# Clock.net
KiCad netlist of a schematic drawn in Altium Designer
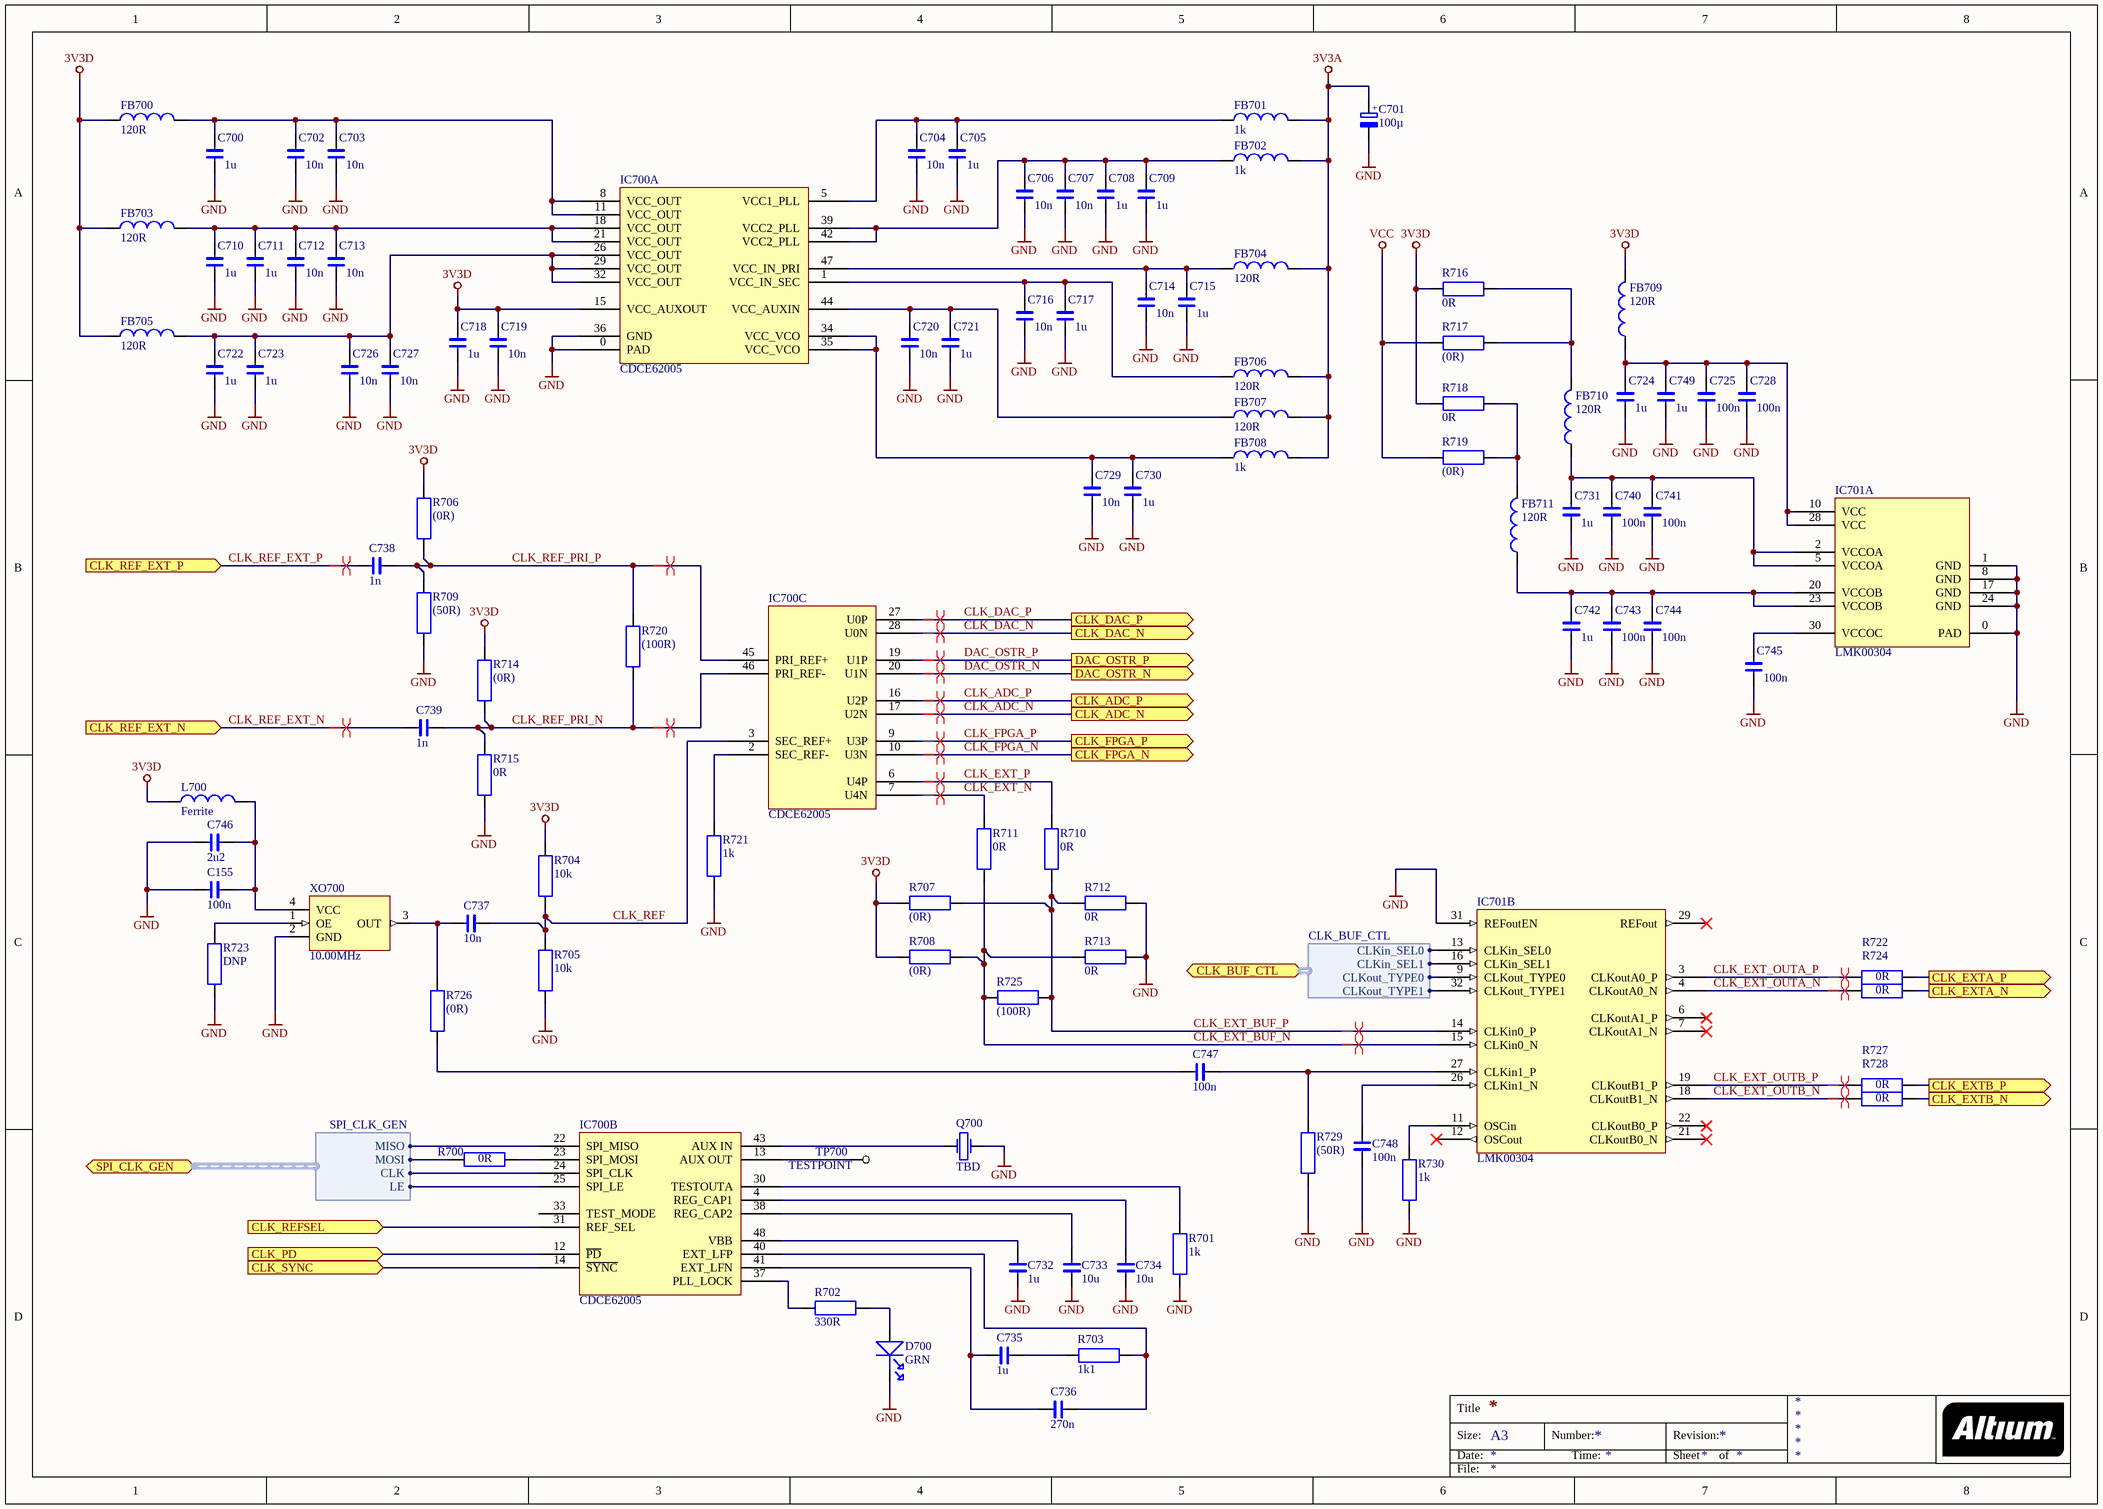
[diagram p0: Clock.SchDoc]

(export (version "E")
  (design (tool "Eeschema 10.0.6"))
  (components
    (comp (ref "C155")
      (value "100n")
      (footprint "0603 SMALL OUTLINE")
      (description "C")
      (libsource (lib "RCL") (part "C"))
    )
    (comp (ref "C700")
      (value "1u")
      (footprint "0603 SMALL OUTLINE")
      (description "C")
      (libsource (lib "RCL") (part "C"))
    )
    (comp (ref "C701")
      (value "100µ")
      (footprint "SMD_ELKO_6.3")
      (description "EEH-ZA1E101XP")
      (libsource (lib "RCL") (part "ELCO"))
    )
    (comp (ref "C702") (value "10n") (footprint "0402") (description "C") (libsource (lib "RCL") (part "C")))
    (comp (ref "C703") (value "10n") (footprint "0402") (description "C") (libsource (lib "RCL") (part "C")))
    (comp (ref "C704") (value "10n") (footprint "0402") (description "C") (libsource (lib "RCL") (part "C")))
    (comp (ref "C705")
      (value "1u")
      (footprint "0603 SMALL OUTLINE")
      (description "C")
      (libsource (lib "RCL") (part "C"))
    )
    (comp (ref "C706") (value "10n") (footprint "0402") (description "C") (libsource (lib "RCL") (part "C")))
    (comp (ref "C707") (value "10n") (footprint "0402") (description "C") (libsource (lib "RCL") (part "C")))
    (comp (ref "C708")
      (value "1u")
      (footprint "0603 SMALL OUTLINE")
      (description "C")
      (libsource (lib "RCL") (part "C"))
    )
    (comp (ref "C709")
      (value "1u")
      (footprint "0603 SMALL OUTLINE")
      (description "C")
      (libsource (lib "RCL") (part "C"))
    )
    (comp (ref "C710")
      (value "1u")
      (footprint "0603 SMALL OUTLINE")
      (description "C")
      (libsource (lib "RCL") (part "C"))
    )
    (comp (ref "C711")
      (value "1u")
      (footprint "0603 SMALL OUTLINE")
      (description "C")
      (libsource (lib "RCL") (part "C"))
    )
    (comp (ref "C712") (value "10n") (footprint "0402") (description "C") (libsource (lib "RCL") (part "C")))
    (comp (ref "C713") (value "10n") (footprint "0402") (description "C") (libsource (lib "RCL") (part "C")))
    (comp (ref "C714") (value "10n") (footprint "0402") (description "C") (libsource (lib "RCL") (part "C")))
    (comp (ref "C715")
      (value "1u")
      (footprint "0603 SMALL OUTLINE")
      (description "C")
      (libsource (lib "RCL") (part "C"))
    )
    (comp (ref "C716") (value "10n") (footprint "0402") (description "C") (libsource (lib "RCL") (part "C")))
    (comp (ref "C717")
      (value "1u")
      (footprint "0603 SMALL OUTLINE")
      (description "C")
      (libsource (lib "RCL") (part "C"))
    )
    (comp (ref "C718")
      (value "1u")
      (footprint "0603 SMALL OUTLINE")
      (description "C")
      (libsource (lib "RCL") (part "C"))
    )
    (comp (ref "C719") (value "10n") (footprint "0402") (description "C") (libsource (lib "RCL") (part "C")))
    (comp (ref "C720") (value "10n") (footprint "0402") (description "C") (libsource (lib "RCL") (part "C")))
    (comp (ref "C721")
      (value "1u")
      (footprint "0603 SMALL OUTLINE")
      (description "C")
      (libsource (lib "RCL") (part "C"))
    )
    (comp (ref "C722")
      (value "1u")
      (footprint "0603 SMALL OUTLINE")
      (description "C")
      (libsource (lib "RCL") (part "C"))
    )
    (comp (ref "C723")
      (value "1u")
      (footprint "0603 SMALL OUTLINE")
      (description "C")
      (libsource (lib "RCL") (part "C"))
    )
    (comp (ref "C724")
      (value "1u")
      (footprint "0603 SMALL OUTLINE")
      (description "C")
      (libsource (lib "RCL") (part "C"))
    )
    (comp (ref "C725") (value "100n") (footprint "0402") (description "C") (libsource (lib "RCL") (part "C")))
    (comp (ref "C726") (value "10n") (footprint "0402") (description "C") (libsource (lib "RCL") (part "C")))
    (comp (ref "C727") (value "10n") (footprint "0402") (description "C") (libsource (lib "RCL") (part "C")))
    (comp (ref "C728") (value "100n") (footprint "0402") (description "C") (libsource (lib "RCL") (part "C")))
    (comp (ref "C729") (value "10n") (footprint "0402") (description "C") (libsource (lib "RCL") (part "C")))
    (comp (ref "C730")
      (value "1u")
      (footprint "0603 SMALL OUTLINE")
      (description "C")
      (libsource (lib "RCL") (part "C"))
    )
    (comp (ref "C731")
      (value "1u")
      (footprint "0603 SMALL OUTLINE")
      (description "C")
      (libsource (lib "RCL") (part "C"))
    )
    (comp (ref "C732")
      (value "1u")
      (footprint "0603 SMALL OUTLINE")
      (description "C")
      (libsource (lib "RCL") (part "C"))
    )
    (comp (ref "C733")
      (value "10u")
      (footprint "0805 SMALL OUTLINE")
      (description "C")
      (libsource (lib "RCL") (part "C"))
    )
    (comp (ref "C734")
      (value "10u")
      (footprint "0805 SMALL OUTLINE")
      (description "C")
      (libsource (lib "RCL") (part "C"))
    )
    (comp (ref "C735")
      (value "1u")
      (footprint "0603 SMALL OUTLINE")
      (description "C")
      (libsource (lib "RCL") (part "C"))
    )
    (comp (ref "C736")
      (value "270n")
      (footprint "0603 SMALL OUTLINE")
      (description "C")
      (libsource (lib "RCL") (part "C"))
    )
    (comp (ref "C737")
      (value "10n")
      (footprint "0603 SMALL OUTLINE")
      (description "C")
      (libsource (lib "RCL") (part "C"))
    )
    (comp (ref "C738")
      (value "1n")
      (footprint "0603 SMALL OUTLINE")
      (description "C")
      (libsource (lib "RCL") (part "C"))
    )
    (comp (ref "C739")
      (value "1n")
      (footprint "0603 SMALL OUTLINE")
      (description "C")
      (libsource (lib "RCL") (part "C"))
    )
    (comp (ref "C740") (value "100n") (footprint "0402") (description "C") (libsource (lib "RCL") (part "C")))
    (comp (ref "C741") (value "100n") (footprint "0402") (description "C") (libsource (lib "RCL") (part "C")))
    (comp (ref "C742")
      (value "1u")
      (footprint "0603 SMALL OUTLINE")
      (description "C")
      (libsource (lib "RCL") (part "C"))
    )
    (comp (ref "C743") (value "100n") (footprint "0402") (description "C") (libsource (lib "RCL") (part "C")))
    (comp (ref "C744") (value "100n") (footprint "0402") (description "C") (libsource (lib "RCL") (part "C")))
    (comp (ref "C745") (value "100n") (footprint "0402") (description "C") (libsource (lib "RCL") (part "C")))
    (comp (ref "C746")
      (value "2u2")
      (footprint "0603 SMALL OUTLINE")
      (description "C")
      (libsource (lib "RCL") (part "C"))
    )
    (comp (ref "C747")
      (value "100n")
      (footprint "0603 SMALL OUTLINE")
      (description "C")
      (libsource (lib "RCL") (part "C"))
    )
    (comp (ref "C748") (value "100n") (footprint "0402") (description "C") (libsource (lib "RCL") (part "C")))
    (comp (ref "C749")
      (value "1u")
      (footprint "0603 SMALL OUTLINE")
      (description "C")
      (libsource (lib "RCL") (part "C"))
    )
    (comp (ref "D700")
      (value "GRN")
      (footprint "LED SMD 0603")
      (description "WURTH 150060VS75000")
      (libsource (lib "OPTO1") (part "LED SMD"))
    )
    (comp (ref "FB700")
      (value "120R")
      (footprint "0805 SMALL OUTLINE")
      (description "L")
      (libsource (lib "RCL") (part "L"))
    )
    (comp (ref "FB701")
      (value "1k")
      (footprint "0805 SMALL OUTLINE")
      (description "L")
      (libsource (lib "RCL") (part "L"))
    )
    (comp (ref "FB702")
      (value "1k")
      (footprint "0805 SMALL OUTLINE")
      (description "L")
      (libsource (lib "RCL") (part "L"))
    )
    (comp (ref "FB703")
      (value "120R")
      (footprint "0805 SMALL OUTLINE")
      (description "L")
      (libsource (lib "RCL") (part "L"))
    )
    (comp (ref "FB704")
      (value "120R")
      (footprint "0805 SMALL OUTLINE")
      (description "L")
      (libsource (lib "RCL") (part "L"))
    )
    (comp (ref "FB705")
      (value "120R")
      (footprint "0805 SMALL OUTLINE")
      (description "L")
      (libsource (lib "RCL") (part "L"))
    )
    (comp (ref "FB706")
      (value "120R")
      (footprint "0805 SMALL OUTLINE")
      (description "L")
      (libsource (lib "RCL") (part "L"))
    )
    (comp (ref "FB707")
      (value "120R")
      (footprint "0805 SMALL OUTLINE")
      (description "L")
      (libsource (lib "RCL") (part "L"))
    )
    (comp (ref "FB708")
      (value "1k")
      (footprint "0805 SMALL OUTLINE")
      (description "L")
      (libsource (lib "RCL") (part "L"))
    )
    (comp (ref "FB709")
      (value "120R")
      (footprint "0805 SMALL OUTLINE")
      (description "L")
      (libsource (lib "RCL") (part "L"))
    )
    (comp (ref "FB710")
      (value "120R")
      (footprint "0805 SMALL OUTLINE")
      (description "L")
      (libsource (lib "RCL") (part "L"))
    )
    (comp (ref "FB711")
      (value "120R")
      (footprint "0805 SMALL OUTLINE")
      (description "L")
      (libsource (lib "RCL") (part "L"))
    )
    (comp (ref "IC700")
      (value "CDCE62005")
      (footprint "48VQFN")
      (description "Five/Ten Output Clock Generator/Jitter Cleaner With Integrated Dual VCOs")
      (libsource (lib "Private") (part "CDCE62005"))
    )
    (comp (ref "IC701")
      (value "LMK00304")
      (footprint "WQFN32_LONG")
      (description "3-GHz 4-Output Differential Clock Buffer/Level Translator")
      (libsource (lib "Private") (part "LMK00304"))
    )
    (comp (ref "L700")
      (value "Ferrite")
      (footprint "0805")
      (description "L")
      (libsource (lib "RCL") (part "L"))
    )
    (comp (ref "Q700")
      (value "TBD")
      (footprint "XTAL_SMD_60_35")
      (description "XX MHz")
      (libsource (lib "RCL") (part "CRYSTAL"))
    )
    (comp (ref "R700")
      (value "0R")
      (footprint "0603 SMALL OUTLINE")
      (description "R")
      (libsource (lib "RCL") (part "R"))
    )
    (comp (ref "R701")
      (value "1k")
      (footprint "0603 SMALL OUTLINE")
      (description "R")
      (libsource (lib "RCL") (part "R"))
    )
    (comp (ref "R702")
      (value "330R")
      (footprint "0603 SMALL OUTLINE")
      (description "R")
      (libsource (lib "RCL") (part "R"))
    )
    (comp (ref "R703")
      (value "1k1")
      (footprint "0603 SMALL OUTLINE")
      (description "R")
      (libsource (lib "RCL") (part "R"))
    )
    (comp (ref "R704")
      (value "10k")
      (footprint "0603 SMALL OUTLINE")
      (description "R")
      (libsource (lib "RCL") (part "R"))
    )
    (comp (ref "R705")
      (value "10k")
      (footprint "0603 SMALL OUTLINE")
      (description "R")
      (libsource (lib "RCL") (part "R"))
    )
    (comp (ref "R706") (value "(0R)") (footprint "0402") (description "R") (libsource (lib "RCL") (part "R")))
    (comp (ref "R707") (value "(0R)") (footprint "0402") (description "R") (libsource (lib "RCL") (part "R")))
    (comp (ref "R708") (value "(0R)") (footprint "0402") (description "R") (libsource (lib "RCL") (part "R")))
    (comp (ref "R709")
      (value "(50R)")
      (footprint "0402")
      (description "R")
      (libsource (lib "RCL") (part "R"))
    )
    (comp (ref "R710") (value "0R") (footprint "0402") (description "R") (libsource (lib "RCL") (part "R")))
    (comp (ref "R711") (value "0R") (footprint "0402") (description "R") (libsource (lib "RCL") (part "R")))
    (comp (ref "R712") (value "0R") (footprint "0402") (description "R") (libsource (lib "RCL") (part "R")))
    (comp (ref "R713") (value "0R") (footprint "0402") (description "R") (libsource (lib "RCL") (part "R")))
    (comp (ref "R714") (value "(0R)") (footprint "0402") (description "R") (libsource (lib "RCL") (part "R")))
    (comp (ref "R715") (value "0R") (footprint "0402") (description "R") (libsource (lib "RCL") (part "R")))
    (comp (ref "R716")
      (value "0R")
      (footprint "0603 SMALL OUTLINE")
      (description "R")
      (libsource (lib "RCL") (part "R"))
    )
    (comp (ref "R717")
      (value "(0R)")
      (footprint "0603 SMALL OUTLINE")
      (description "R")
      (libsource (lib "RCL") (part "R"))
    )
    (comp (ref "R718")
      (value "0R")
      (footprint "0603 SMALL OUTLINE")
      (description "R")
      (libsource (lib "RCL") (part "R"))
    )
    (comp (ref "R719")
      (value "(0R)")
      (footprint "0603 SMALL OUTLINE")
      (description "R")
      (libsource (lib "RCL") (part "R"))
    )
    (comp (ref "R720")
      (value "(100R)")
      (footprint "0402")
      (description "R")
      (libsource (lib "RCL") (part "R"))
    )
    (comp (ref "R721")
      (value "1k")
      (footprint "0603 SMALL OUTLINE")
      (description "R")
      (libsource (lib "RCL") (part "R"))
    )
    (comp (ref "R722") (value "0R") (footprint "0402") (description "R") (libsource (lib "RCL") (part "R")))
    (comp (ref "R723")
      (value "DNP")
      (footprint "0603 SMALL OUTLINE")
      (description "R")
      (libsource (lib "RCL") (part "R"))
    )
    (comp (ref "R724") (value "0R") (footprint "0402") (description "R") (libsource (lib "RCL") (part "R")))
    (comp (ref "R725")
      (value "(100R)")
      (footprint "0402")
      (description "R")
      (libsource (lib "RCL") (part "R"))
    )
    (comp (ref "R726")
      (value "(0R)")
      (footprint "0603 SMALL OUTLINE")
      (description "R")
      (libsource (lib "RCL") (part "R"))
    )
    (comp (ref "R727") (value "0R") (footprint "0402") (description "R") (libsource (lib "RCL") (part "R")))
    (comp (ref "R728") (value "0R") (footprint "0402") (description "R") (libsource (lib "RCL") (part "R")))
    (comp (ref "R729")
      (value "(50R)")
      (footprint "0402")
      (description "R")
      (libsource (lib "RCL") (part "R"))
    )
    (comp (ref "R730")
      (value "1k")
      (footprint "0603 SMALL OUTLINE")
      (description "R")
      (libsource (lib "RCL") (part "R"))
    )
    (comp (ref "TP700")
      (value "TESTPOINT")
      (footprint "TEST_PAD_50")
      (libsource (lib "CONNECT1") (part "TESTPOINT"))
    )
    (comp (ref "XO700")
      (value "10.00MHz")
      (footprint "AST3TQ")
      (description "AST3TQ-10.00MHz-1")
      (libsource (lib "SPECIAL1") (part "OSZILLATOR_4P SMD"))
    )
  )
  (nets
    (net (code "3") (name "/CLK") (class "Default")
      (node (ref "IC700") (pin "24") (pinfunction "SPI_CLK_24") (pintype "passive"))
    )
    (net (code "4") (name "/CLK_ADC_N") (class "Default")
      (node (ref "IC700") (pin "17") (pinfunction "U2N_17") (pintype "passive"))
    )
    (net (code "5") (name "/CLK_ADC_P") (class "Default")
      (node (ref "IC700") (pin "16") (pinfunction "U2P_16") (pintype "passive"))
    )
    (net (code "6") (name "/CLK_DAC_N") (class "Default")
      (node (ref "IC700") (pin "28") (pinfunction "U0N_28") (pintype "passive"))
    )
    (net (code "7") (name "/CLK_DAC_P") (class "Default")
      (node (ref "IC700") (pin "27") (pinfunction "U0P_27") (pintype "passive"))
    )
    (net (code "8") (name "/CLK_EXTA_N") (class "Default")
      (node (ref "R724") (pin "2") (pinfunction "2_2") (pintype "passive"))
    )
    (net (code "9") (name "/CLK_EXTA_P") (class "Default")
      (node (ref "R722") (pin "2") (pinfunction "2_2") (pintype "passive"))
    )
    (net (code "10") (name "/CLK_EXTB_N") (class "Default")
      (node (ref "R728") (pin "2") (pinfunction "2_2") (pintype "passive"))
    )
    (net (code "11") (name "/CLK_EXTB_P") (class "Default")
      (node (ref "R727") (pin "2") (pinfunction "2_2") (pintype "passive"))
    )
    (net (code "12") (name "/CLK_EXT_BUF_N") (class "Default")
      (node (ref "IC701") (pin "15") (pinfunction "CLKin0_N_15") (pintype "input"))
      (node (ref "R708") (pin "1") (pinfunction "1_1") (pintype "passive"))
      (node (ref "R711") (pin "1") (pinfunction "1_1") (pintype "passive"))
      (node (ref "R713") (pin "2") (pinfunction "2_2") (pintype "passive"))
      (node (ref "R725") (pin "1") (pinfunction "1_1") (pintype "passive"))
    )
    (net (code "13") (name "/CLK_EXT_BUF_P") (class "Default")
      (node (ref "IC701") (pin "14") (pinfunction "CLKin0_P_14") (pintype "input"))
      (node (ref "R707") (pin "1") (pinfunction "1_1") (pintype "passive"))
      (node (ref "R710") (pin "1") (pinfunction "1_1") (pintype "passive"))
      (node (ref "R712") (pin "2") (pinfunction "2_2") (pintype "passive"))
      (node (ref "R725") (pin "2") (pinfunction "2_2") (pintype "passive"))
    )
    (net (code "14") (name "/CLK_EXT_N") (class "Default")
      (node (ref "IC700") (pin "7") (pinfunction "U4N_7") (pintype "passive"))
      (node (ref "R711") (pin "2") (pinfunction "2_2") (pintype "passive"))
    )
    (net (code "15") (name "/CLK_EXT_OUTA_N") (class "Default")
      (node (ref "IC701") (pin "4") (pinfunction "CLKoutA0_N_4") (pintype "output"))
      (node (ref "R724") (pin "1") (pinfunction "1_1") (pintype "passive"))
    )
    (net (code "16") (name "/CLK_EXT_OUTA_P") (class "Default")
      (node (ref "IC701") (pin "3") (pinfunction "CLKoutA0_P_3") (pintype "output"))
      (node (ref "R722") (pin "1") (pinfunction "1_1") (pintype "passive"))
    )
    (net (code "17") (name "/CLK_EXT_OUTB_N") (class "Default")
      (node (ref "IC701") (pin "18") (pinfunction "CLKoutB1_N_18") (pintype "output"))
      (node (ref "R728") (pin "1") (pinfunction "1_1") (pintype "passive"))
    )
    (net (code "18") (name "/CLK_EXT_OUTB_P") (class "Default")
      (node (ref "IC701") (pin "19") (pinfunction "CLKoutB1_P_19") (pintype "output"))
      (node (ref "R727") (pin "1") (pinfunction "1_1") (pintype "passive"))
    )
    (net (code "19") (name "/CLK_EXT_P") (class "Default")
      (node (ref "IC700") (pin "6") (pinfunction "U4P_6") (pintype "passive"))
      (node (ref "R710") (pin "2") (pinfunction "2_2") (pintype "passive"))
    )
    (net (code "20") (name "/CLK_FPGA_N") (class "Default")
      (node (ref "IC700") (pin "10") (pinfunction "U3N_10") (pintype "passive"))
    )
    (net (code "21") (name "/CLK_FPGA_P") (class "Default")
      (node (ref "IC700") (pin "9") (pinfunction "U3P_9") (pintype "passive"))
    )
    (net (code "22") (name "/CLK_PD") (class "Default")
      (node (ref "IC700") (pin "12") (pinfunction "~{PD}_12") (pintype "passive"))
    )
    (net (code "23") (name "/CLK_REF") (class "Default")
      (node (ref "C737") (pin "2") (pinfunction "2_2") (pintype "passive"))
      (node (ref "IC700") (pin "3") (pinfunction "SEC_REF+_3") (pintype "passive"))
      (node (ref "R704") (pin "1") (pinfunction "1_1") (pintype "passive"))
      (node (ref "R705") (pin "2") (pinfunction "2_2") (pintype "passive"))
    )
    (net (code "24") (name "/CLK_REFSEL") (class "Default")
      (node (ref "IC700") (pin "31") (pinfunction "REF_SEL_31") (pintype "passive"))
    )
    (net (code "25") (name "/CLK_REF_EXT_N") (class "Default")
      (node (ref "C739") (pin "1") (pinfunction "1_1") (pintype "passive"))
    )
    (net (code "26") (name "/CLK_REF_EXT_P") (class "Default")
      (node (ref "C738") (pin "1") (pinfunction "1_1") (pintype "passive"))
    )
    (net (code "27") (name "/CLK_REF_PRI_N") (class "Default")
      (node (ref "C739") (pin "2") (pinfunction "2_2") (pintype "passive"))
      (node (ref "IC700") (pin "46") (pinfunction "PRI_REF-_46") (pintype "passive"))
      (node (ref "R714") (pin "1") (pinfunction "1_1") (pintype "passive"))
      (node (ref "R715") (pin "2") (pinfunction "2_2") (pintype "passive"))
      (node (ref "R720") (pin "1") (pinfunction "1_1") (pintype "passive"))
    )
    (net (code "28") (name "/CLK_REF_PRI_P") (class "Default")
      (node (ref "C738") (pin "2") (pinfunction "2_2") (pintype "passive"))
      (node (ref "IC700") (pin "45") (pinfunction "PRI_REF+_45") (pintype "passive"))
      (node (ref "R706") (pin "1") (pinfunction "1_1") (pintype "passive"))
      (node (ref "R709") (pin "2") (pinfunction "2_2") (pintype "passive"))
      (node (ref "R720") (pin "2") (pinfunction "2_2") (pintype "passive"))
    )
    (net (code "29") (name "/CLK_SYNC") (class "Default")
      (node (ref "IC700") (pin "14") (pinfunction "~{SYNC}_14") (pintype "passive"))
    )
    (net (code "30") (name "/CLKin_SEL0") (class "Default")
      (node (ref "IC701") (pin "13") (pinfunction "CLKin_SEL0_13") (pintype "input"))
    )
    (net (code "31") (name "/CLKin_SEL1") (class "Default")
      (node (ref "IC701") (pin "16") (pinfunction "CLKin_SEL1_16") (pintype "input"))
    )
    (net (code "32") (name "/CLKout_TYPE0") (class "Default")
      (node (ref "IC701") (pin "9") (pinfunction "CLKout_TYPE0_9") (pintype "input"))
    )
    (net (code "33") (name "/CLKout_TYPE1") (class "Default")
      (node (ref "IC701") (pin "32") (pinfunction "CLKout_TYPE1_32") (pintype "input"))
    )
    (net (code "34") (name "/DAC_OSTR_N") (class "Default")
      (node (ref "IC700") (pin "20") (pinfunction "U1N_20") (pintype "passive"))
    )
    (net (code "35") (name "/DAC_OSTR_P") (class "Default")
      (node (ref "IC700") (pin "19") (pinfunction "U1P_19") (pintype "passive"))
    )
    (net (code "36") (name "/LE") (class "Default")
      (node (ref "IC700") (pin "25") (pinfunction "SPI_LE_25") (pintype "passive"))
    )
    (net (code "37") (name "/MISO") (class "Default")
      (node (ref "IC700") (pin "22") (pinfunction "SPI_MISO_22") (pintype "passive"))
    )
    (net (code "38") (name "/MOSI") (class "Default")
      (node (ref "R700") (pin "1") (pinfunction "1_1") (pintype "passive"))
    )
    (net (code "41") (name "3V3A") (class "Default")
      (node (ref "C701") (pin "1") (pinfunction "+_1") (pintype "passive"))
      (node (ref "FB701") (pin "2") (pinfunction "2_2") (pintype "passive"))
      (node (ref "FB702") (pin "2") (pinfunction "2_2") (pintype "passive"))
      (node (ref "FB704") (pin "2") (pinfunction "2_2") (pintype "passive"))
      (node (ref "FB706") (pin "2") (pinfunction "2_2") (pintype "passive"))
      (node (ref "FB707") (pin "2") (pinfunction "2_2") (pintype "passive"))
      (node (ref "FB708") (pin "2") (pinfunction "2_2") (pintype "passive"))
    )
    (net (code "42") (name "3V3D") (class "Default")
      (node (ref "C718") (pin "1") (pinfunction "1_1") (pintype "passive"))
      (node (ref "C719") (pin "1") (pinfunction "1_1") (pintype "passive"))
      (node (ref "FB700") (pin "1") (pinfunction "1_1") (pintype "passive"))
      (node (ref "FB703") (pin "1") (pinfunction "1_1") (pintype "passive"))
      (node (ref "FB705") (pin "1") (pinfunction "1_1") (pintype "passive"))
      (node (ref "FB709") (pin "2") (pinfunction "2_2") (pintype "passive"))
      (node (ref "IC700") (pin "15") (pinfunction "VCC_AUXOUT_15") (pintype "passive"))
      (node (ref "L700") (pin "1") (pinfunction "1_1") (pintype "passive"))
      (node (ref "R704") (pin "2") (pinfunction "2_2") (pintype "passive"))
      (node (ref "R706") (pin "2") (pinfunction "2_2") (pintype "passive"))
      (node (ref "R707") (pin "2") (pinfunction "2_2") (pintype "passive"))
      (node (ref "R708") (pin "2") (pinfunction "2_2") (pintype "passive"))
      (node (ref "R714") (pin "2") (pinfunction "2_2") (pintype "passive"))
      (node (ref "R716") (pin "2") (pinfunction "2_2") (pintype "passive"))
      (node (ref "R718") (pin "2") (pinfunction "2_2") (pintype "passive"))
    )
    (net (code "43") (name "GND") (class "Default")
      (node (ref "C155") (pin "2") (pinfunction "2_2") (pintype "passive"))
      (node (ref "C700") (pin "2") (pinfunction "2_2") (pintype "passive"))
      (node (ref "C701") (pin "2") (pinfunction "-_2") (pintype "passive"))
      (node (ref "C702") (pin "2") (pinfunction "2_2") (pintype "passive"))
      (node (ref "C703") (pin "2") (pinfunction "2_2") (pintype "passive"))
      (node (ref "C704") (pin "2") (pinfunction "2_2") (pintype "passive"))
      (node (ref "C705") (pin "2") (pinfunction "2_2") (pintype "passive"))
      (node (ref "C706") (pin "2") (pinfunction "2_2") (pintype "passive"))
      (node (ref "C707") (pin "2") (pinfunction "2_2") (pintype "passive"))
      (node (ref "C708") (pin "2") (pinfunction "2_2") (pintype "passive"))
      (node (ref "C709") (pin "2") (pinfunction "2_2") (pintype "passive"))
      (node (ref "C710") (pin "2") (pinfunction "2_2") (pintype "passive"))
      (node (ref "C711") (pin "2") (pinfunction "2_2") (pintype "passive"))
      (node (ref "C712") (pin "2") (pinfunction "2_2") (pintype "passive"))
      (node (ref "C713") (pin "2") (pinfunction "2_2") (pintype "passive"))
      (node (ref "C714") (pin "2") (pinfunction "2_2") (pintype "passive"))
      (node (ref "C715") (pin "2") (pinfunction "2_2") (pintype "passive"))
      (node (ref "C716") (pin "2") (pinfunction "2_2") (pintype "passive"))
      (node (ref "C717") (pin "2") (pinfunction "2_2") (pintype "passive"))
      (node (ref "C718") (pin "2") (pinfunction "2_2") (pintype "passive"))
      (node (ref "C719") (pin "2") (pinfunction "2_2") (pintype "passive"))
      (node (ref "C720") (pin "2") (pinfunction "2_2") (pintype "passive"))
      (node (ref "C721") (pin "2") (pinfunction "2_2") (pintype "passive"))
      (node (ref "C722") (pin "2") (pinfunction "2_2") (pintype "passive"))
      (node (ref "C723") (pin "2") (pinfunction "2_2") (pintype "passive"))
      (node (ref "C724") (pin "2") (pinfunction "2_2") (pintype "passive"))
      (node (ref "C725") (pin "2") (pinfunction "2_2") (pintype "passive"))
      (node (ref "C726") (pin "2") (pinfunction "2_2") (pintype "passive"))
      (node (ref "C727") (pin "2") (pinfunction "2_2") (pintype "passive"))
      (node (ref "C728") (pin "2") (pinfunction "2_2") (pintype "passive"))
      (node (ref "C729") (pin "2") (pinfunction "2_2") (pintype "passive"))
      (node (ref "C730") (pin "2") (pinfunction "2_2") (pintype "passive"))
      (node (ref "C731") (pin "2") (pinfunction "2_2") (pintype "passive"))
      (node (ref "C732") (pin "2") (pinfunction "2_2") (pintype "passive"))
      (node (ref "C733") (pin "2") (pinfunction "2_2") (pintype "passive"))
      (node (ref "C734") (pin "2") (pinfunction "2_2") (pintype "passive"))
      (node (ref "C740") (pin "2") (pinfunction "2_2") (pintype "passive"))
      (node (ref "C741") (pin "2") (pinfunction "2_2") (pintype "passive"))
      (node (ref "C742") (pin "2") (pinfunction "2_2") (pintype "passive"))
      (node (ref "C743") (pin "2") (pinfunction "2_2") (pintype "passive"))
      (node (ref "C744") (pin "2") (pinfunction "2_2") (pintype "passive"))
      (node (ref "C745") (pin "2") (pinfunction "2_2") (pintype "passive"))
      (node (ref "C746") (pin "2") (pinfunction "2_2") (pintype "passive"))
      (node (ref "C748") (pin "2") (pinfunction "2_2") (pintype "passive"))
      (node (ref "C749") (pin "2") (pinfunction "2_2") (pintype "passive"))
      (node (ref "D700") (pin "K") (pinfunction "K_K") (pintype "passive"))
      (node (ref "IC700") (pin "0") (pinfunction "PAD_0") (pintype "passive"))
      (node (ref "IC700") (pin "36") (pinfunction "GND_36") (pintype "passive"))
      (node (ref "IC701") (pin "0") (pinfunction "PAD_0") (pintype "power_in"))
      (node (ref "IC701") (pin "1") (pinfunction "GND_1") (pintype "power_in"))
      (node (ref "IC701") (pin "17") (pinfunction "GND_17") (pintype "power_in"))
      (node (ref "IC701") (pin "24") (pinfunction "GND_24") (pintype "power_in"))
      (node (ref "IC701") (pin "31") (pinfunction "REFoutEN_31") (pintype "input"))
      (node (ref "IC701") (pin "8") (pinfunction "GND_8") (pintype "power_in"))
      (node (ref "Q700") (pin "2") (pinfunction "2_2") (pintype "passive"))
      (node (ref "R701") (pin "2") (pinfunction "2_2") (pintype "passive"))
      (node (ref "R705") (pin "1") (pinfunction "1_1") (pintype "passive"))
      (node (ref "R709") (pin "1") (pinfunction "1_1") (pintype "passive"))
      (node (ref "R712") (pin "1") (pinfunction "1_1") (pintype "passive"))
      (node (ref "R713") (pin "1") (pinfunction "1_1") (pintype "passive"))
      (node (ref "R715") (pin "1") (pinfunction "1_1") (pintype "passive"))
      (node (ref "R721") (pin "1") (pinfunction "1_1") (pintype "passive"))
      (node (ref "R723") (pin "1") (pinfunction "1_1") (pintype "passive"))
      (node (ref "R729") (pin "1") (pinfunction "1_1") (pintype "passive"))
      (node (ref "R730") (pin "1") (pinfunction "1_1") (pintype "passive"))
      (node (ref "XO700") (pin "2") (pinfunction "GND_2") (pintype "power_in"))
    )
    (net (code "44") (name "Net-(C700-Pad1)") (class "Default")
      (node (ref "C700") (pin "1") (pinfunction "1_1") (pintype "passive"))
      (node (ref "C702") (pin "1") (pinfunction "1_1") (pintype "passive"))
      (node (ref "C703") (pin "1") (pinfunction "1_1") (pintype "passive"))
      (node (ref "FB700") (pin "2") (pinfunction "2_2") (pintype "passive"))
      (node (ref "IC700") (pin "11") (pinfunction "VCC_OUT_11") (pintype "passive"))
      (node (ref "IC700") (pin "8") (pinfunction "VCC_OUT_8") (pintype "passive"))
    )
    (net (code "45") (name "Net-(C706-Pad1)") (class "Default")
      (node (ref "C706") (pin "1") (pinfunction "1_1") (pintype "passive"))
      (node (ref "C707") (pin "1") (pinfunction "1_1") (pintype "passive"))
      (node (ref "C708") (pin "1") (pinfunction "1_1") (pintype "passive"))
      (node (ref "C709") (pin "1") (pinfunction "1_1") (pintype "passive"))
      (node (ref "FB702") (pin "1") (pinfunction "1_1") (pintype "passive"))
      (node (ref "IC700") (pin "39") (pinfunction "VCC2_PLL_39") (pintype "passive"))
      (node (ref "IC700") (pin "42") (pinfunction "VCC2_PLL_42") (pintype "passive"))
    )
    (net (code "46") (name "Net-(C710-Pad1)") (class "Default")
      (node (ref "C710") (pin "1") (pinfunction "1_1") (pintype "passive"))
      (node (ref "C711") (pin "1") (pinfunction "1_1") (pintype "passive"))
      (node (ref "C712") (pin "1") (pinfunction "1_1") (pintype "passive"))
      (node (ref "C713") (pin "1") (pinfunction "1_1") (pintype "passive"))
      (node (ref "FB703") (pin "2") (pinfunction "2_2") (pintype "passive"))
      (node (ref "IC700") (pin "18") (pinfunction "VCC_OUT_18") (pintype "passive"))
      (node (ref "IC700") (pin "21") (pinfunction "VCC_OUT_21") (pintype "passive"))
    )
    (net (code "47") (name "Net-(C722-Pad1)") (class "Default")
      (node (ref "C722") (pin "1") (pinfunction "1_1") (pintype "passive"))
      (node (ref "C723") (pin "1") (pinfunction "1_1") (pintype "passive"))
      (node (ref "C726") (pin "1") (pinfunction "1_1") (pintype "passive"))
      (node (ref "C727") (pin "1") (pinfunction "1_1") (pintype "passive"))
      (node (ref "FB705") (pin "2") (pinfunction "2_2") (pintype "passive"))
      (node (ref "IC700") (pin "26") (pinfunction "VCC_OUT_26") (pintype "passive"))
      (node (ref "IC700") (pin "29") (pinfunction "VCC_OUT_29") (pintype "passive"))
      (node (ref "IC700") (pin "32") (pinfunction "VCC_OUT_32") (pintype "passive"))
    )
    (net (code "48") (name "Net-(C724-Pad1)") (class "Default")
      (node (ref "C724") (pin "1") (pinfunction "1_1") (pintype "passive"))
      (node (ref "C725") (pin "1") (pinfunction "1_1") (pintype "passive"))
      (node (ref "C728") (pin "1") (pinfunction "1_1") (pintype "passive"))
      (node (ref "C749") (pin "1") (pinfunction "1_1") (pintype "passive"))
      (node (ref "FB709") (pin "1") (pinfunction "1_1") (pintype "passive"))
      (node (ref "IC701") (pin "10") (pinfunction "VCC_10") (pintype "power_in"))
      (node (ref "IC701") (pin "28") (pinfunction "VCC_28") (pintype "power_in"))
    )
    (net (code "49") (name "Net-(C729-Pad1)") (class "Default")
      (node (ref "C729") (pin "1") (pinfunction "1_1") (pintype "passive"))
      (node (ref "C730") (pin "1") (pinfunction "1_1") (pintype "passive"))
      (node (ref "FB708") (pin "1") (pinfunction "1_1") (pintype "passive"))
      (node (ref "IC700") (pin "34") (pinfunction "VCC_VCO_34") (pintype "passive"))
      (node (ref "IC700") (pin "35") (pinfunction "VCC_VCO_35") (pintype "passive"))
    )
    (net (code "50") (name "Net-(C731-Pad1)") (class "Default")
      (node (ref "C731") (pin "1") (pinfunction "1_1") (pintype "passive"))
      (node (ref "C740") (pin "1") (pinfunction "1_1") (pintype "passive"))
      (node (ref "C741") (pin "1") (pinfunction "1_1") (pintype "passive"))
      (node (ref "FB710") (pin "1") (pinfunction "1_1") (pintype "passive"))
      (node (ref "IC701") (pin "2") (pinfunction "VCCOA_2") (pintype "power_in"))
      (node (ref "IC701") (pin "5") (pinfunction "VCCOA_5") (pintype "power_in"))
    )
    (net (code "51") (name "Net-(C735-Pad2)") (class "Default")
      (node (ref "C735") (pin "2") (pinfunction "2_2") (pintype "passive"))
      (node (ref "R703") (pin "2") (pinfunction "2_2") (pintype "passive"))
    )
    (net (code "52") (name "Net-(C742-Pad1)") (class "Default")
      (node (ref "C742") (pin "1") (pinfunction "1_1") (pintype "passive"))
      (node (ref "C743") (pin "1") (pinfunction "1_1") (pintype "passive"))
      (node (ref "C744") (pin "1") (pinfunction "1_1") (pintype "passive"))
      (node (ref "FB711") (pin "1") (pinfunction "1_1") (pintype "passive"))
      (node (ref "IC701") (pin "20") (pinfunction "VCCOB_20") (pintype "power_in"))
      (node (ref "IC701") (pin "23") (pinfunction "VCCOB_23") (pintype "power_in"))
    )
    (net (code "53") (name "Net-(C747-Pad1)") (class "Default")
      (node (ref "C747") (pin "1") (pinfunction "1_1") (pintype "passive"))
      (node (ref "R726") (pin "2") (pinfunction "2_2") (pintype "passive"))
    )
    (net (code "54") (name "Net-(D700-PadA)") (class "Default")
      (node (ref "D700") (pin "A") (pinfunction "A_A") (pintype "passive"))
      (node (ref "R702") (pin "1") (pinfunction "1_1") (pintype "passive"))
    )
    (net (code "55") (name "Net-(FB710-Pad2)") (class "Default")
      (node (ref "FB710") (pin "2") (pinfunction "2_2") (pintype "passive"))
      (node (ref "R716") (pin "1") (pinfunction "1_1") (pintype "passive"))
      (node (ref "R717") (pin "1") (pinfunction "1_1") (pintype "passive"))
    )
    (net (code "56") (name "Net-(FB711-Pad2)") (class "Default")
      (node (ref "FB711") (pin "2") (pinfunction "2_2") (pintype "passive"))
      (node (ref "R718") (pin "1") (pinfunction "1_1") (pintype "passive"))
      (node (ref "R719") (pin "1") (pinfunction "1_1") (pintype "passive"))
    )
    (net (code "57") (name "Net-(IC700A-VCC1_PLL)") (class "Default")
      (node (ref "C704") (pin "1") (pinfunction "1_1") (pintype "passive"))
      (node (ref "C705") (pin "1") (pinfunction "1_1") (pintype "passive"))
      (node (ref "FB701") (pin "1") (pinfunction "1_1") (pintype "passive"))
      (node (ref "IC700") (pin "5") (pinfunction "VCC1_PLL_5") (pintype "passive"))
    )
    (net (code "58") (name "Net-(IC700A-VCC_AUXIN)") (class "Default")
      (node (ref "C720") (pin "1") (pinfunction "1_1") (pintype "passive"))
      (node (ref "C721") (pin "1") (pinfunction "1_1") (pintype "passive"))
      (node (ref "FB707") (pin "1") (pinfunction "1_1") (pintype "passive"))
      (node (ref "IC700") (pin "44") (pinfunction "VCC_AUXIN_44") (pintype "passive"))
    )
    (net (code "59") (name "Net-(IC700A-VCC_IN_PRI)") (class "Default")
      (node (ref "C714") (pin "1") (pinfunction "1_1") (pintype "passive"))
      (node (ref "C715") (pin "1") (pinfunction "1_1") (pintype "passive"))
      (node (ref "FB704") (pin "1") (pinfunction "1_1") (pintype "passive"))
      (node (ref "IC700") (pin "47") (pinfunction "VCC_IN_PRI_47") (pintype "passive"))
    )
    (net (code "60") (name "Net-(IC700A-VCC_IN_SEC)") (class "Default")
      (node (ref "C716") (pin "1") (pinfunction "1_1") (pintype "passive"))
      (node (ref "C717") (pin "1") (pinfunction "1_1") (pintype "passive"))
      (node (ref "FB706") (pin "1") (pinfunction "1_1") (pintype "passive"))
      (node (ref "IC700") (pin "1") (pinfunction "VCC_IN_SEC_1") (pintype "passive"))
    )
    (net (code "61") (name "Net-(IC700B-AUX_IN)") (class "Default")
      (node (ref "IC700") (pin "43") (pinfunction "AUX_IN_43") (pintype "passive"))
      (node (ref "Q700") (pin "1") (pinfunction "1_1") (pintype "passive"))
    )
    (net (code "62") (name "Net-(IC700B-AUX_OUT)") (class "Default")
      (node (ref "IC700") (pin "13") (pinfunction "AUX_OUT_13") (pintype "passive"))
      (node (ref "TP700") (pin "1") (pintype "passive"))
    )
    (net (code "63") (name "Net-(IC700B-EXT_LFN)") (class "Default")
      (node (ref "C735") (pin "1") (pinfunction "1_1") (pintype "passive"))
      (node (ref "C736") (pin "2") (pinfunction "2_2") (pintype "passive"))
      (node (ref "IC700") (pin "41") (pinfunction "EXT_LFN_41") (pintype "passive"))
    )
    (net (code "64") (name "Net-(IC700B-EXT_LFP)") (class "Default")
      (node (ref "C736") (pin "1") (pinfunction "1_1") (pintype "passive"))
      (node (ref "IC700") (pin "40") (pinfunction "EXT_LFP_40") (pintype "passive"))
      (node (ref "R703") (pin "1") (pinfunction "1_1") (pintype "passive"))
    )
    (net (code "65") (name "Net-(IC700B-PLL_LOCK)") (class "Default")
      (node (ref "IC700") (pin "37") (pinfunction "PLL_LOCK_37") (pintype "passive"))
      (node (ref "R702") (pin "2") (pinfunction "2_2") (pintype "passive"))
    )
    (net (code "66") (name "Net-(IC700B-REG_CAP1)") (class "Default")
      (node (ref "C734") (pin "1") (pinfunction "1_1") (pintype "passive"))
      (node (ref "IC700") (pin "4") (pinfunction "REG_CAP1_4") (pintype "passive"))
    )
    (net (code "67") (name "Net-(IC700B-REG_CAP2)") (class "Default")
      (node (ref "C733") (pin "1") (pinfunction "1_1") (pintype "passive"))
      (node (ref "IC700") (pin "38") (pinfunction "REG_CAP2_38") (pintype "passive"))
    )
    (net (code "68") (name "Net-(IC700B-SPI_MOSI)") (class "Default")
      (node (ref "IC700") (pin "23") (pinfunction "SPI_MOSI_23") (pintype "passive"))
      (node (ref "R700") (pin "2") (pinfunction "2_2") (pintype "passive"))
    )
    (net (code "69") (name "Net-(IC700B-TESTOUTA)") (class "Default")
      (node (ref "IC700") (pin "30") (pinfunction "TESTOUTA_30") (pintype "passive"))
      (node (ref "R701") (pin "1") (pinfunction "1_1") (pintype "passive"))
    )
    (net (code "70") (name "Net-(IC700B-VBB)") (class "Default")
      (node (ref "C732") (pin "1") (pinfunction "1_1") (pintype "passive"))
      (node (ref "IC700") (pin "48") (pinfunction "VBB_48") (pintype "passive"))
    )
    (net (code "71") (name "Net-(IC700C-SEC_REF-)") (class "Default")
      (node (ref "IC700") (pin "2") (pinfunction "SEC_REF-_2") (pintype "passive"))
      (node (ref "R721") (pin "2") (pinfunction "2_2") (pintype "passive"))
    )
    (net (code "72") (name "Net-(IC701A-VCCOC)") (class "Default")
      (node (ref "C745") (pin "1") (pinfunction "1_1") (pintype "passive"))
      (node (ref "IC701") (pin "30") (pinfunction "VCCOC_30") (pintype "power_in"))
    )
    (net (code "73") (name "Net-(IC701B-CLKin1_N)") (class "Default")
      (node (ref "C748") (pin "1") (pinfunction "1_1") (pintype "passive"))
      (node (ref "IC701") (pin "26") (pinfunction "CLKin1_N_26") (pintype "input"))
    )
    (net (code "74") (name "Net-(IC701B-CLKin1_P)") (class "Default")
      (node (ref "C747") (pin "2") (pinfunction "2_2") (pintype "passive"))
      (node (ref "IC701") (pin "27") (pinfunction "CLKin1_P_27") (pintype "input"))
      (node (ref "R729") (pin "2") (pinfunction "2_2") (pintype "passive"))
    )
    (net (code "75") (name "Net-(IC701B-OSCin)") (class "Default")
      (node (ref "IC701") (pin "11") (pinfunction "OSCin_11") (pintype "input"))
      (node (ref "R730") (pin "2") (pinfunction "2_2") (pintype "passive"))
    )
    (net (code "76") (name "Net-(XO700-OE)") (class "Default")
      (node (ref "R723") (pin "2") (pinfunction "2_2") (pintype "passive"))
      (node (ref "XO700") (pin "1") (pinfunction "OE_1") (pintype "input"))
    )
    (net (code "77") (name "Net-(XO700-OUT)") (class "Default")
      (node (ref "C737") (pin "1") (pinfunction "1_1") (pintype "passive"))
      (node (ref "R726") (pin "1") (pinfunction "1_1") (pintype "passive"))
      (node (ref "XO700") (pin "3") (pinfunction "OUT_3") (pintype "output"))
    )
    (net (code "78") (name "Net-(XO700-VCC)") (class "Default")
      (node (ref "C155") (pin "1") (pinfunction "1_1") (pintype "passive"))
      (node (ref "C746") (pin "1") (pinfunction "1_1") (pintype "passive"))
      (node (ref "L700") (pin "2") (pinfunction "2_2") (pintype "passive"))
      (node (ref "XO700") (pin "4") (pinfunction "VCC_4") (pintype "power_in"))
    )
    (net (code "79") (name "VCC") (class "Default")
      (node (ref "R717") (pin "2") (pinfunction "2_2") (pintype "passive"))
      (node (ref "R719") (pin "2") (pinfunction "2_2") (pintype "passive"))
    )
    (net (code "80") (name "unconnected-(IC700B-TEST_MODE-Pad33)") (class "Default")
      (node (ref "IC700") (pin "33") (pinfunction "TEST_MODE_33") (pintype "passive"))
    )
    (net (code "81") (name "unconnected-(IC701B-CLKoutA1_N-Pad7)") (class "Default")
      (node (ref "IC701") (pin "7") (pinfunction "CLKoutA1_N_7") (pintype "output+no_connect"))
    )
    (net (code "82") (name "unconnected-(IC701B-CLKoutA1_P-Pad6)") (class "Default")
      (node (ref "IC701") (pin "6") (pinfunction "CLKoutA1_P_6") (pintype "output+no_connect"))
    )
    (net (code "83") (name "unconnected-(IC701B-CLKoutB0_N-Pad21)") (class "Default")
      (node (ref "IC701") (pin "21") (pinfunction "CLKoutB0_N_21") (pintype "output+no_connect"))
    )
    (net (code "84") (name "unconnected-(IC701B-CLKoutB0_P-Pad22)") (class "Default")
      (node (ref "IC701") (pin "22") (pinfunction "CLKoutB0_P_22") (pintype "output+no_connect"))
    )
    (net (code "85") (name "unconnected-(IC701B-OSCout-Pad12)") (class "Default")
      (node (ref "IC701") (pin "12") (pinfunction "OSCout_12") (pintype "output+no_connect"))
    )
    (net (code "86") (name "unconnected-(IC701B-REFout-Pad29)") (class "Default")
      (node (ref "IC701") (pin "29") (pinfunction "REFout_29") (pintype "output+no_connect"))
    )
  )
)
